# SerialBTBridge.net
KiCad netlist of a schematic drawn in EAGLE
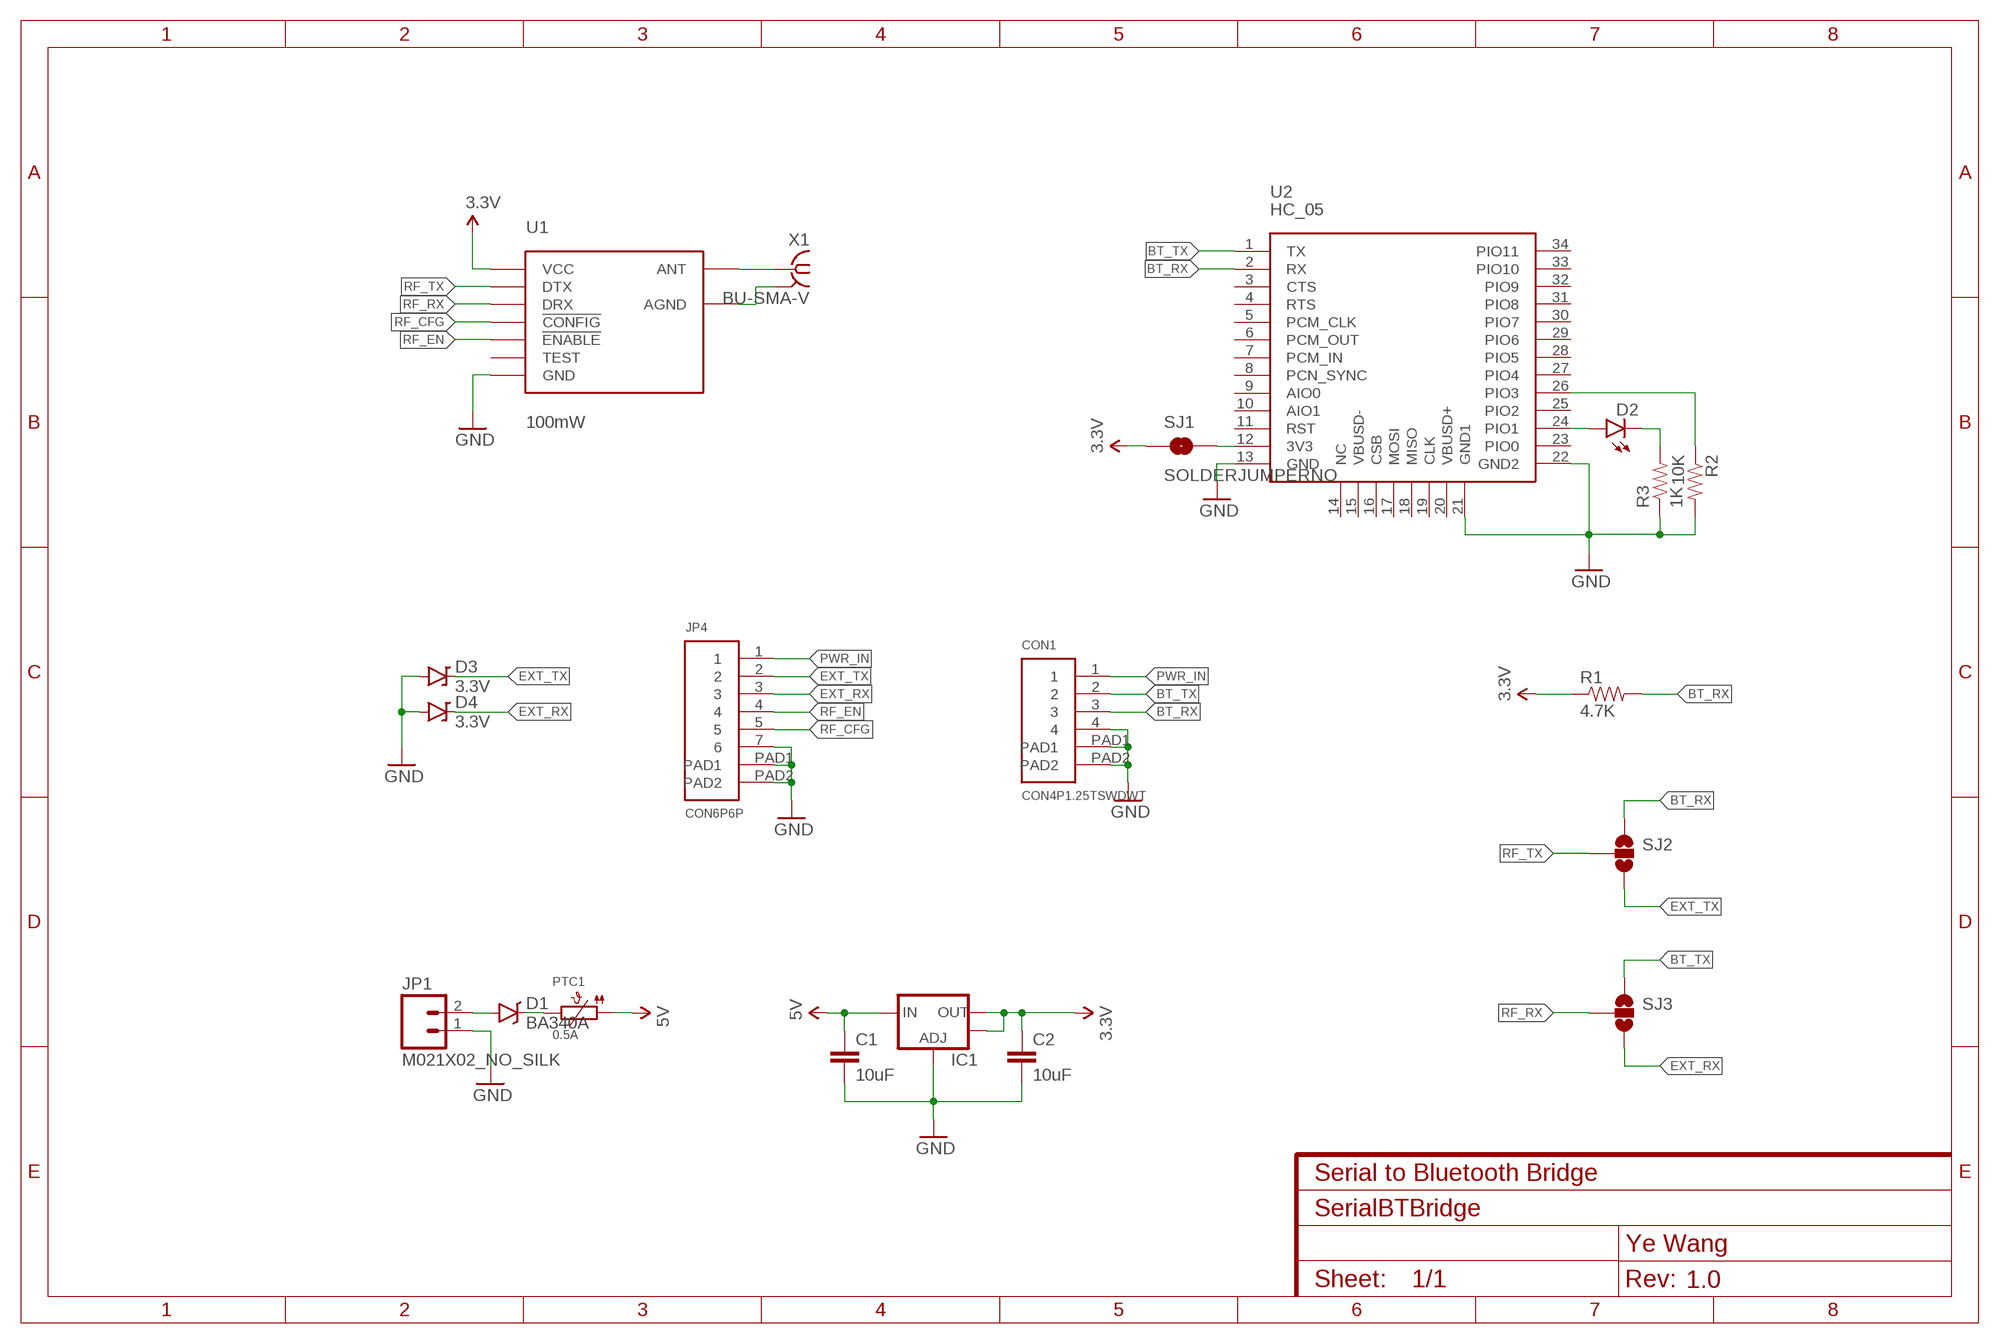
[diagram p0: schematic, sheet 1]

(export (version "E")
  (design (tool "Eeschema 10.0.6"))
  (components
    (comp (ref "C1")
      (value "10uF")
      (footprint "eagle-import:0805-CAP")
      (libsource (lib "eagle-import") (part "CAP0805W"))
    )
    (comp (ref "C2")
      (value "10uF")
      (footprint "eagle-import:0603-CAP")
      (libsource (lib "eagle-import") (part "10UF-6.3V-20%(0603)"))
    )
    (comp (ref "CON1")
      (value "CON4P1.25TSWDWT")
      (footprint "eagle-import:1.25T4P")
      (libsource (lib "eagle-import") (part "CON4P1.25TSWDWT"))
    )
    (comp (ref "D1")
      (value "BA340A")
      (footprint "eagle-import:SMA-DIODE")
      (libsource (lib "eagle-import") (part "B340A"))
    )
    (comp (ref "D2")
      (value "LED0603")
      (footprint "eagle-import:LED-0603")
      (libsource (lib "eagle-import") (part "LED0603"))
    )
    (comp (ref "D3")
      (value "3.3V")
      (footprint "eagle-import:SOD-323")
      (libsource (lib "eagle-import") (part "DIODE-ZENER3.3V"))
    )
    (comp (ref "D4")
      (value "3.3V")
      (footprint "eagle-import:SOD-323")
      (libsource (lib "eagle-import") (part "DIODE-ZENER3.3V"))
    )
    (comp (ref "IC1")
      (value "V_REG_LM1117SOT223")
      (footprint "eagle-import:SOT223")
      (libsource (lib "eagle-import") (part "V_REG_LM1117SOT223"))
    )
    (comp (ref "JP1")
      (value "M021X02_NO_SILK")
      (footprint "eagle-import:1X02_NO_SILK")
      (libsource (lib "eagle-import") (part "M021X02_NO_SILK"))
    )
    (comp (ref "JP4")
      (value "CON6P6P")
      (footprint "eagle-import:1.25T6P")
      (libsource (lib "eagle-import") (part "CON6P6P"))
    )
    (comp (ref "PTC1")
      (value "0.5A")
      (footprint "eagle-import:PTC1812")
      (libsource (lib "eagle-import") (part "PTC1812"))
    )
    (comp (ref "R1")
      (value "4.7K")
      (footprint "eagle-import:0603-RES")
      (libsource (lib "eagle-import") (part "4.7KOHM-1/10W-1%(0603)"))
    )
    (comp (ref "R2")
      (value "10K")
      (footprint "eagle-import:0603-RES")
      (libsource (lib "eagle-import") (part "10KOHM-1/10W-1%(0603)0603"))
    )
    (comp (ref "R3")
      (value "1K")
      (footprint "eagle-import:0603-RES")
      (libsource (lib "eagle-import") (part "1KOHM-1/10W-1%(0603)"))
    )
    (comp (ref "SJ1")
      (value "SOLDERJUMPERNO")
      (footprint "eagle-import:SJ_2S-NO")
      (libsource (lib "eagle-import") (part "SOLDERJUMPERNO"))
    )
    (comp (ref "SJ2")
      (value "SOLDERJUMPER_2WAYS")
      (footprint "eagle-import:SJ_3")
      (libsource (lib "eagle-import") (part "SOLDERJUMPER_2WAYS"))
    )
    (comp (ref "SJ3")
      (value "SOLDERJUMPER_2WAYS")
      (footprint "eagle-import:SJ_3")
      (libsource (lib "eagle-import") (part "SOLDERJUMPER_2WAYS"))
    )
    (comp (ref "U1")
      (value "100mW")
      (footprint "eagle-import:HM-TRP-SMD")
      (libsource (lib "eagle-import") (part "HM-TRPSMD"))
    )
    (comp (ref "U2")
      (value "HC_05")
      (footprint "eagle-import:BLUETOOTH_SMD")
      (libsource (lib "eagle-import") (part "HC_05"))
    )
    (comp (ref "X1")
      (value "BU-SMA-V")
      (footprint "eagle-import:BU-SMA-V")
      (libsource (lib "eagle-import") (part "BU-SMA-V"))
    )
  )
  (nets
    (net (code "1") (name "3.3V") (class "Default")
      (node (ref "C2") (pin "1") (pinfunction "1_1") (pintype "passive"))
      (node (ref "IC1") (pin "2") (pinfunction "OUT_2") (pintype "output"))
      (node (ref "IC1") (pin "4") (pinfunction "OUT_4") (pintype "output"))
      (node (ref "R1") (pin "1") (pinfunction "1_1") (pintype "passive"))
      (node (ref "SJ1") (pin "1") (pinfunction "1_1") (pintype "passive"))
      (node (ref "U1") (pin "VCC") (pinfunction "VCC_VCC") (pintype "power_in"))
    )
    (net (code "2") (name "5V") (class "Default")
      (node (ref "C1") (pin "P$1") (pinfunction "1_P$1") (pintype "passive"))
      (node (ref "IC1") (pin "3") (pinfunction "IN_3") (pintype "input"))
      (node (ref "PTC1") (pin "P$1") (pinfunction "1_P$1") (pintype "passive"))
    )
    (net (code "3") (name "BT_RX") (class "Default")
      (node (ref "CON1") (pin "3") (pinfunction "3_3") (pintype "bidirectional"))
      (node (ref "R1") (pin "2") (pinfunction "2_2") (pintype "passive"))
      (node (ref "SJ2") (pin "1") (pinfunction "1_1") (pintype "passive"))
      (node (ref "U2") (pin "2") (pinfunction "RX_2") (pintype "bidirectional"))
    )
    (net (code "4") (name "BT_TX") (class "Default")
      (node (ref "CON1") (pin "2") (pinfunction "2_2") (pintype "bidirectional"))
      (node (ref "SJ3") (pin "1") (pinfunction "1_1") (pintype "passive"))
      (node (ref "U2") (pin "1") (pinfunction "TX_1") (pintype "bidirectional"))
    )
    (net (code "5") (name "EXT_RX") (class "Default")
      (node (ref "D4") (pin "C") (pinfunction "C_C") (pintype "passive"))
      (node (ref "JP4") (pin "3") (pinfunction "3_3") (pintype "bidirectional"))
      (node (ref "SJ3") (pin "3") (pinfunction "3_3") (pintype "passive"))
    )
    (net (code "6") (name "EXT_TX") (class "Default")
      (node (ref "D3") (pin "C") (pinfunction "C_C") (pintype "passive"))
      (node (ref "JP4") (pin "2") (pinfunction "2_2") (pintype "bidirectional"))
      (node (ref "SJ2") (pin "3") (pinfunction "3_3") (pintype "passive"))
    )
    (net (code "7") (name "GND") (class "Default")
      (node (ref "C1") (pin "P$2") (pinfunction "2_P$2") (pintype "passive"))
      (node (ref "C2") (pin "2") (pinfunction "2_2") (pintype "passive"))
      (node (ref "CON1") (pin "4") (pinfunction "4_4") (pintype "bidirectional"))
      (node (ref "CON1") (pin "PAD1") (pinfunction "PAD1_PAD1") (pintype "bidirectional"))
      (node (ref "CON1") (pin "PAD2") (pinfunction "PAD2_PAD2") (pintype "bidirectional"))
      (node (ref "D3") (pin "A") (pinfunction "A_A") (pintype "passive"))
      (node (ref "D4") (pin "A") (pinfunction "A_A") (pintype "passive"))
      (node (ref "IC1") (pin "1") (pinfunction "ADJ_1") (pintype "input"))
      (node (ref "JP1") (pin "1") (pinfunction "1_1") (pintype "passive"))
      (node (ref "JP4") (pin "7") (pinfunction "6_7") (pintype "bidirectional"))
      (node (ref "JP4") (pin "PAD1") (pinfunction "PAD1_PAD1") (pintype "bidirectional"))
      (node (ref "JP4") (pin "PAD2") (pinfunction "PAD2_PAD2") (pintype "bidirectional"))
      (node (ref "R2") (pin "2") (pinfunction "2_2") (pintype "passive"))
      (node (ref "R3") (pin "1") (pinfunction "1_1") (pintype "passive"))
      (node (ref "U1") (pin "GND") (pinfunction "GND_GND") (pintype "power_in"))
      (node (ref "U2") (pin "13") (pinfunction "GND_13") (pintype "bidirectional"))
      (node (ref "U2") (pin "21") (pinfunction "GND1_21") (pintype "bidirectional"))
      (node (ref "U2") (pin "22") (pinfunction "GND2_22") (pintype "bidirectional"))
    )
    (net (code "8") (name "Net-(D2-PadC)") (class "Default")
      (node (ref "D2") (pin "C") (pinfunction "C_C") (pintype "passive"))
      (node (ref "R3") (pin "2") (pinfunction "2_2") (pintype "passive"))
    )
    (net (code "9") (name "Net-(PTC1-2)") (class "Default")
      (node (ref "D1") (pin "C") (pinfunction "C_C") (pintype "passive"))
      (node (ref "PTC1") (pin "P$2") (pinfunction "2_P$2") (pintype "passive"))
    )
    (net (code "10") (name "Net-(U1-PadAGND)") (class "Default")
      (node (ref "U1") (pin "AGND") (pinfunction "AGND_AGND") (pintype "power_in"))
      (node (ref "X1") (pin "2") (pinfunction "2_2") (pintype "passive"))
      (node (ref "X1") (pin "3") (pinfunction "2_3") (pintype "passive"))
      (node (ref "X1") (pin "4") (pinfunction "2_4") (pintype "passive"))
      (node (ref "X1") (pin "5") (pinfunction "2_5") (pintype "passive"))
    )
    (net (code "11") (name "Net-(U1-PadANT)") (class "Default")
      (node (ref "U1") (pin "ANT") (pinfunction "ANT_ANT") (pintype "bidirectional"))
      (node (ref "X1") (pin "1") (pinfunction "1_1") (pintype "passive"))
    )
    (net (code "12") (name "Net-(U2-3V3)") (class "Default")
      (node (ref "SJ1") (pin "2") (pinfunction "2_2") (pintype "passive"))
      (node (ref "U2") (pin "12") (pinfunction "3V3_12") (pintype "bidirectional"))
    )
    (net (code "13") (name "Net-(U2-PIO1)") (class "Default")
      (node (ref "D2") (pin "A") (pinfunction "A_A") (pintype "passive"))
      (node (ref "U2") (pin "24") (pinfunction "PIO1_24") (pintype "bidirectional"))
    )
    (net (code "14") (name "Net-(U2-PIO3)") (class "Default")
      (node (ref "R2") (pin "1") (pinfunction "1_1") (pintype "passive"))
      (node (ref "U2") (pin "26") (pinfunction "PIO3_26") (pintype "bidirectional"))
    )
    (net (code "15") (name "PWR_IN") (class "Default")
      (node (ref "CON1") (pin "1") (pinfunction "1_1") (pintype "bidirectional"))
      (node (ref "D1") (pin "A") (pinfunction "A_A") (pintype "passive"))
      (node (ref "JP1") (pin "2") (pinfunction "2_2") (pintype "passive"))
      (node (ref "JP4") (pin "1") (pinfunction "1_1") (pintype "bidirectional"))
    )
    (net (code "16") (name "RF_CFG") (class "Default")
      (node (ref "JP4") (pin "5") (pinfunction "5_5") (pintype "bidirectional"))
      (node (ref "U1") (pin "!CONFIG") (pinfunction "~{CONFIG}_!CONFIG") (pintype "input"))
    )
    (net (code "17") (name "RF_EN") (class "Default")
      (node (ref "JP4") (pin "4") (pinfunction "4_4") (pintype "bidirectional"))
      (node (ref "U1") (pin "!ENABLE") (pinfunction "~{ENABLE}_!ENABLE") (pintype "input"))
    )
    (net (code "18") (name "RF_RX") (class "Default")
      (node (ref "SJ3") (pin "2") (pinfunction "2_2") (pintype "passive"))
      (node (ref "U1") (pin "DRX") (pinfunction "DRX_DRX") (pintype "input"))
    )
    (net (code "19") (name "RF_TX") (class "Default")
      (node (ref "SJ2") (pin "2") (pinfunction "2_2") (pintype "passive"))
      (node (ref "U1") (pin "DTX") (pinfunction "DTX_DTX") (pintype "output"))
    )
    (net (code "20") (name "unconnected-(U1-PadTEST)") (class "Default")
      (node (ref "U1") (pin "TEST") (pinfunction "TEST_TEST") (pintype "no_connect"))
    )
    (net (code "21") (name "unconnected-(U2-AIO0-Pad9)") (class "Default")
      (node (ref "U2") (pin "9") (pinfunction "AIO0_9") (pintype "bidirectional"))
    )
    (net (code "22") (name "unconnected-(U2-AIO1-Pad10)") (class "Default")
      (node (ref "U2") (pin "10") (pinfunction "AIO1_10") (pintype "bidirectional"))
    )
    (net (code "23") (name "unconnected-(U2-CLK-Pad19)") (class "Default")
      (node (ref "U2") (pin "19") (pinfunction "CLK_19") (pintype "bidirectional"))
    )
    (net (code "24") (name "unconnected-(U2-CSB-Pad16)") (class "Default")
      (node (ref "U2") (pin "16") (pinfunction "CSB_16") (pintype "bidirectional"))
    )
    (net (code "25") (name "unconnected-(U2-CTS-Pad3)") (class "Default")
      (node (ref "U2") (pin "3") (pinfunction "CTS_3") (pintype "bidirectional"))
    )
    (net (code "26") (name "unconnected-(U2-MISO-Pad18)") (class "Default")
      (node (ref "U2") (pin "18") (pinfunction "MISO_18") (pintype "bidirectional"))
    )
    (net (code "27") (name "unconnected-(U2-MOSI-Pad17)") (class "Default")
      (node (ref "U2") (pin "17") (pinfunction "MOSI_17") (pintype "bidirectional"))
    )
    (net (code "28") (name "unconnected-(U2-NC-Pad14)") (class "Default")
      (node (ref "U2") (pin "14") (pinfunction "NC_14") (pintype "bidirectional"))
    )
    (net (code "29") (name "unconnected-(U2-PCM_CLK-Pad5)") (class "Default")
      (node (ref "U2") (pin "5") (pinfunction "PCM_CLK_5") (pintype "bidirectional"))
    )
    (net (code "30") (name "unconnected-(U2-PCM_IN-Pad7)") (class "Default")
      (node (ref "U2") (pin "7") (pinfunction "PCM_IN_7") (pintype "bidirectional"))
    )
    (net (code "31") (name "unconnected-(U2-PCM_OUT-Pad6)") (class "Default")
      (node (ref "U2") (pin "6") (pinfunction "PCM_OUT_6") (pintype "bidirectional"))
    )
    (net (code "32") (name "unconnected-(U2-PCN_SYNC-Pad8)") (class "Default")
      (node (ref "U2") (pin "8") (pinfunction "PCN_SYNC_8") (pintype "bidirectional"))
    )
    (net (code "33") (name "unconnected-(U2-PIO0-Pad23)") (class "Default")
      (node (ref "U2") (pin "23") (pinfunction "PIO0_23") (pintype "bidirectional"))
    )
    (net (code "34") (name "unconnected-(U2-PIO2-Pad25)") (class "Default")
      (node (ref "U2") (pin "25") (pinfunction "PIO2_25") (pintype "bidirectional"))
    )
    (net (code "35") (name "unconnected-(U2-PIO4-Pad27)") (class "Default")
      (node (ref "U2") (pin "27") (pinfunction "PIO4_27") (pintype "bidirectional"))
    )
    (net (code "36") (name "unconnected-(U2-PIO5-Pad28)") (class "Default")
      (node (ref "U2") (pin "28") (pinfunction "PIO5_28") (pintype "bidirectional"))
    )
    (net (code "37") (name "unconnected-(U2-PIO6-Pad29)") (class "Default")
      (node (ref "U2") (pin "29") (pinfunction "PIO6_29") (pintype "bidirectional"))
    )
    (net (code "38") (name "unconnected-(U2-PIO7-Pad30)") (class "Default")
      (node (ref "U2") (pin "30") (pinfunction "PIO7_30") (pintype "bidirectional"))
    )
    (net (code "39") (name "unconnected-(U2-PIO8-Pad31)") (class "Default")
      (node (ref "U2") (pin "31") (pinfunction "PIO8_31") (pintype "bidirectional"))
    )
    (net (code "40") (name "unconnected-(U2-PIO9-Pad32)") (class "Default")
      (node (ref "U2") (pin "32") (pinfunction "PIO9_32") (pintype "bidirectional"))
    )
    (net (code "41") (name "unconnected-(U2-PIO10-Pad33)") (class "Default")
      (node (ref "U2") (pin "33") (pinfunction "PIO10_33") (pintype "bidirectional"))
    )
    (net (code "42") (name "unconnected-(U2-PIO11-Pad34)") (class "Default")
      (node (ref "U2") (pin "34") (pinfunction "PIO11_34") (pintype "bidirectional"))
    )
    (net (code "43") (name "unconnected-(U2-RST-Pad11)") (class "Default")
      (node (ref "U2") (pin "11") (pinfunction "RST_11") (pintype "bidirectional"))
    )
    (net (code "44") (name "unconnected-(U2-RTS-Pad4)") (class "Default")
      (node (ref "U2") (pin "4") (pinfunction "RTS_4") (pintype "bidirectional"))
    )
    (net (code "45") (name "unconnected-(U2-VBUSD+-Pad20)") (class "Default")
      (node (ref "U2") (pin "20") (pinfunction "VBUSD+_20") (pintype "bidirectional"))
    )
    (net (code "46") (name "unconnected-(U2-VBUSD--Pad15)") (class "Default")
      (node (ref "U2") (pin "15") (pinfunction "VBUSD-_15") (pintype "bidirectional"))
    )
  )
)
